# dv_mcu_analog_lpf.net
KiCad netlist of a schematic drawn in Altium Designer
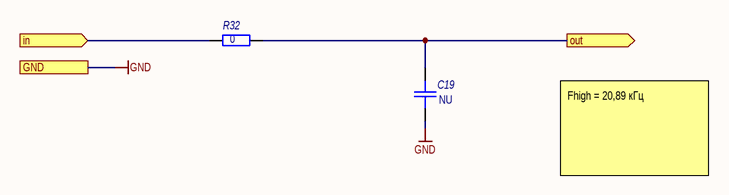
[diagram p0: dv_mcu_analog_lpf.SchDoc]

(export (version "E")
  (design (tool "Eeschema 10.0.6"))
  (components
    (comp (ref "C19")
      (value "NU")
      (footprint "SMD_C0805")
      (description "Capacitor")
      (fields (field (name "Comment") "K10-79"))
      (libsource (lib "Passive") (part "Capacitor"))
    )
    (comp (ref "R32")
      (value "0")
      (footprint "SMD_0805")
      (description "Resistor")
      (fields (field (name "Comment") "OSM R1-12"))
      (libsource (lib "Passive") (part "Resistor"))
    )
  )
  (nets
    (net (code "1") (name "/in") (class "Default")
      (node (ref "R32") (pin "1") (pinfunction "1_1") (pintype "passive"))
    )
    (net (code "2") (name "/out") (class "Default")
      (node (ref "C19") (pin "2") (pinfunction "2_2") (pintype "passive"))
      (node (ref "R32") (pin "2") (pinfunction "2_2") (pintype "passive"))
    )
    (net (code "3") (name "GND") (class "Default")
      (node (ref "C19") (pin "1") (pinfunction "1_1") (pintype "passive"))
    )
  )
)
